# Supply_DAC.net
KiCad netlist of a schematic drawn in Altium Designer
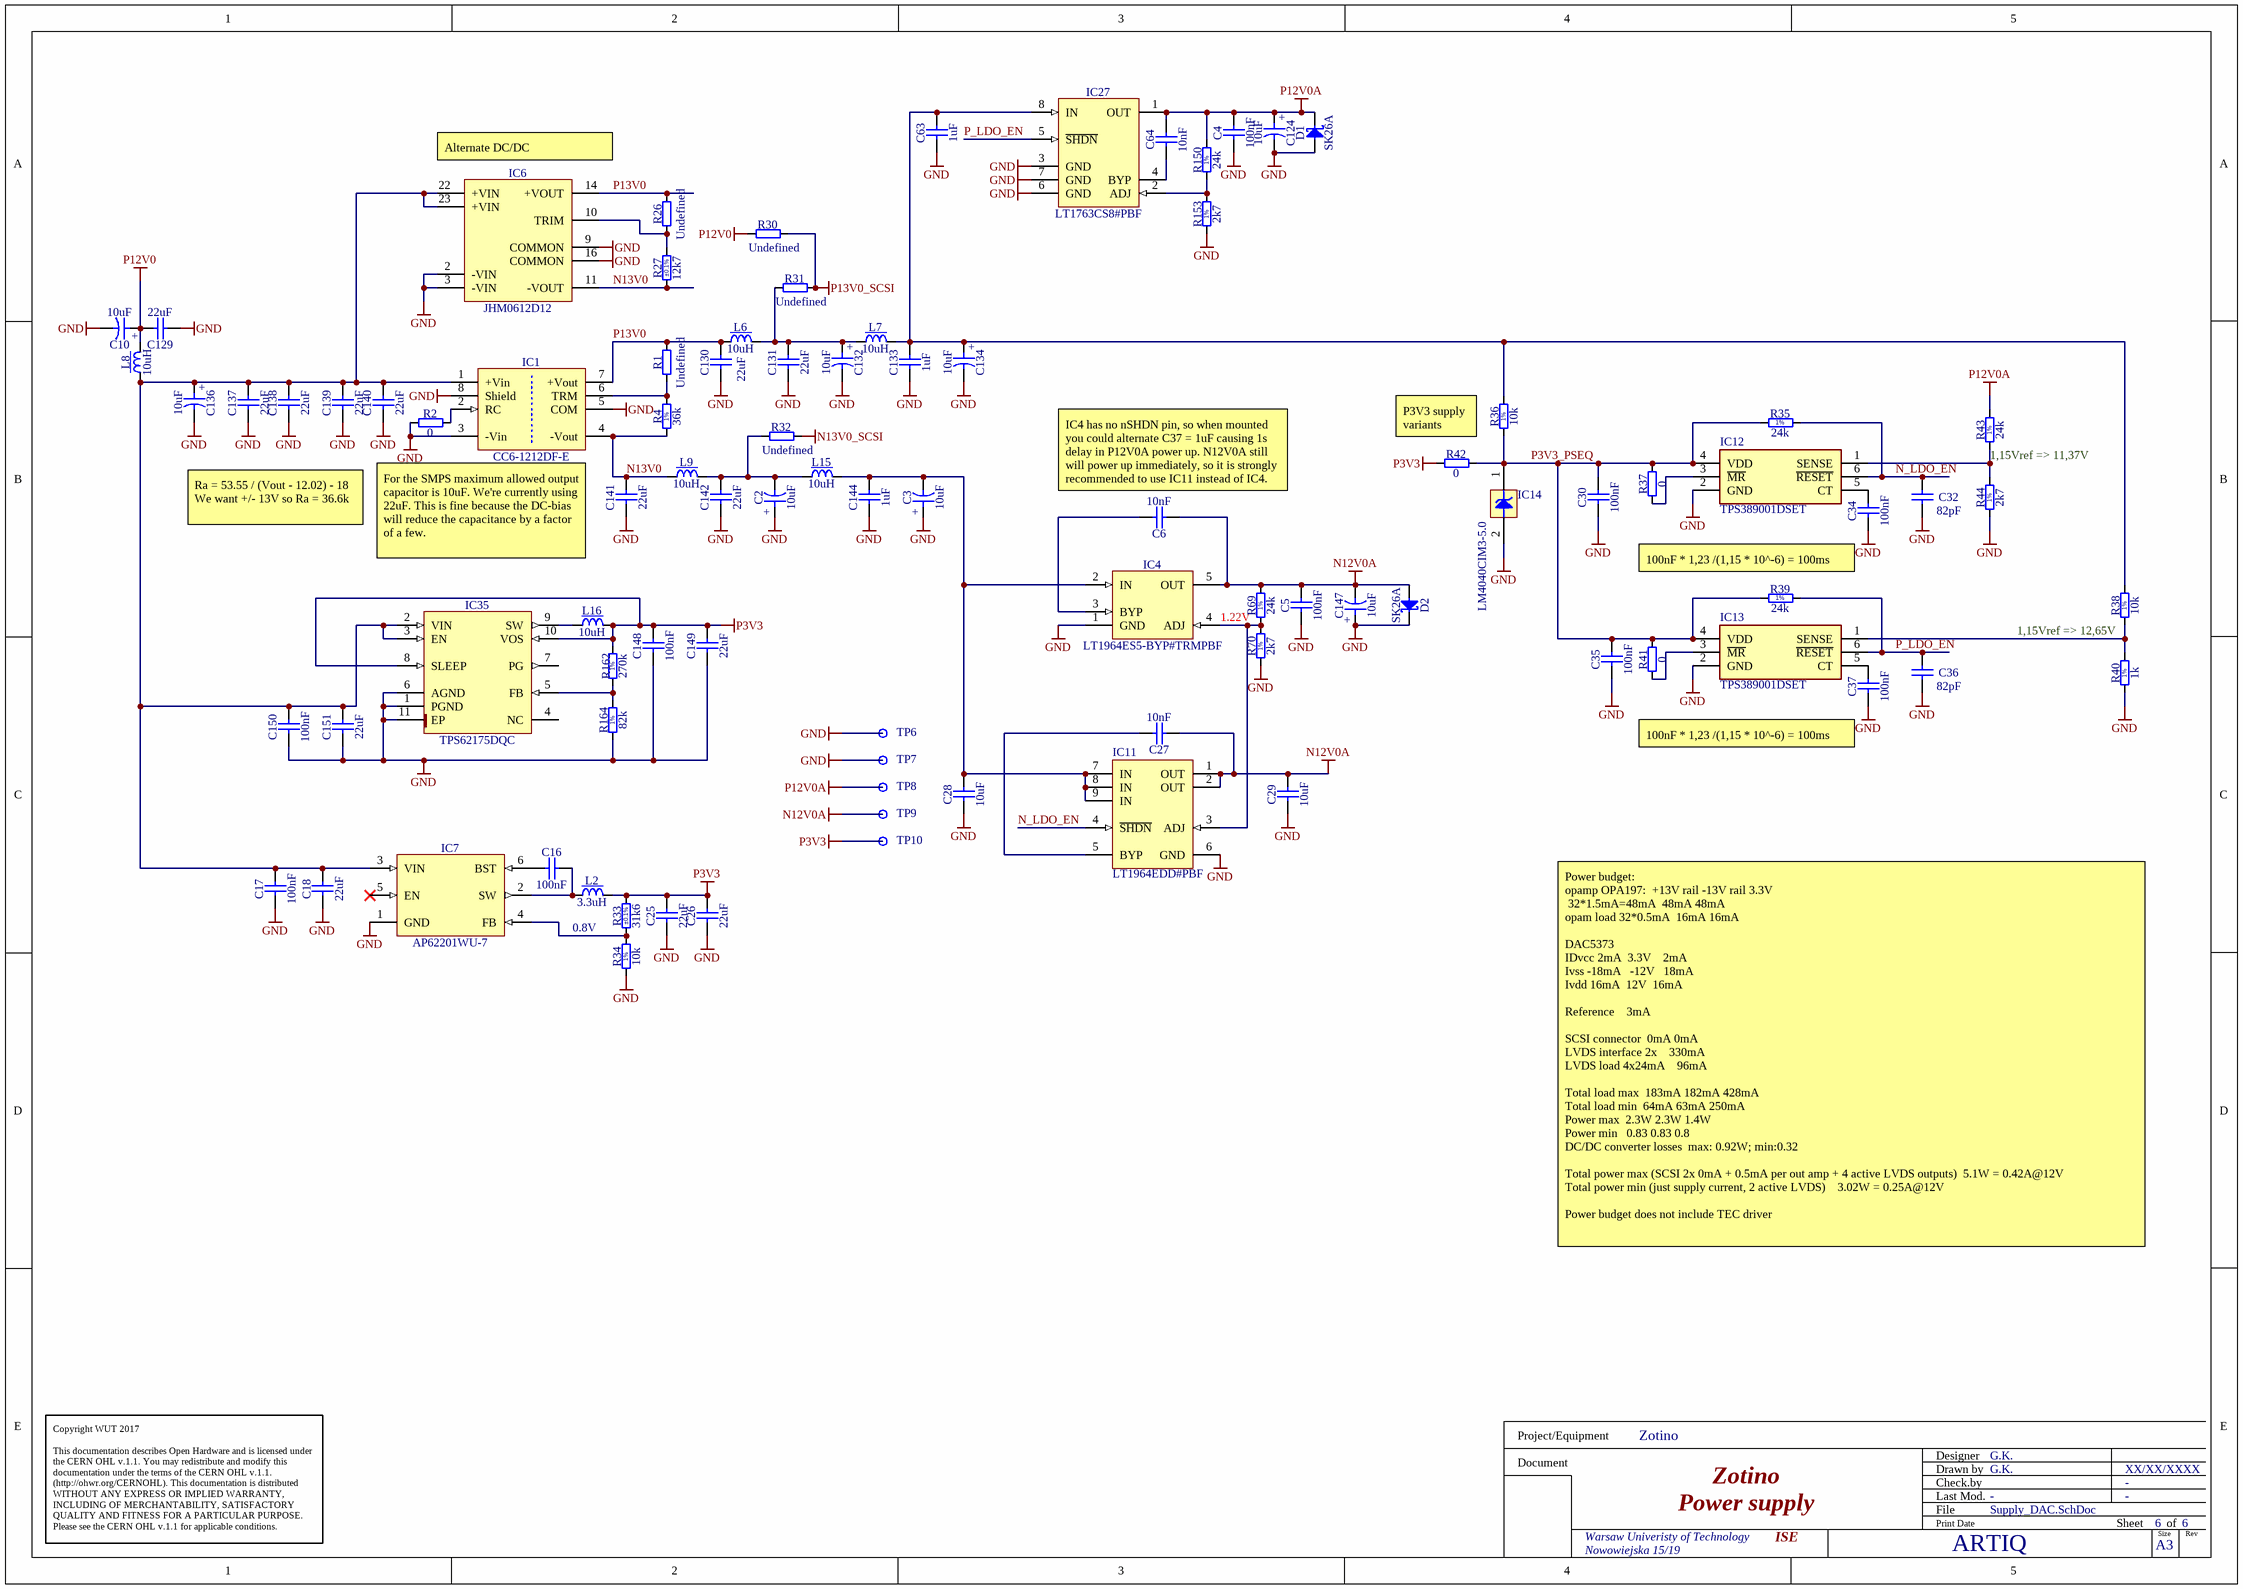
[diagram p0: Supply_DAC.SchDoc]

(export (version "E")
  (design (tool "Eeschema 10.0.6"))
  (components
    (comp (ref "C2")
      (value "10uF")
      (footprint "CAPMP3216X180N")
      (description "Polarised capacitor")
      (fields
        (field (name "PART NUMBER") "CTE3216-18_10UF_16V_20%_AVX_TCJ")
        (field (name "VOLTAGE") "16V")
        (field (name "AUTHOR") "CERN DEM JLC")
      )
      (libsource (lib "Capacitors") (part "Capacitor - polarized"))
    )
    (comp (ref "C3")
      (value "10uF")
      (footprint "CAPMP3216X180N")
      (description "Polarised capacitor")
      (fields
        (field (name "PART NUMBER") "CTE3216-18_10UF_16V_20%_AVX_TCJ")
        (field (name "VOLTAGE") "16V")
        (field (name "AUTHOR") "CERN DEM JLC")
      )
      (libsource (lib "Capacitors") (part "Capacitor - polarized"))
    )
    (comp (ref "C4")
      (value "100nF")
      (footprint "CAPC1005X55N")
      (description "Non-polarised capacitor")
      (fields
        (field (name "PART NUMBER") "CC0402_100NF_16V_10%_X5R")
        (field (name "VOLTAGE") "16V")
        (field (name "AUTHOR") "CERN DEM JLC")
      )
      (libsource (lib "Capacitors") (part "Capacitor - non polarized"))
    )
    (comp (ref "C5")
      (value "100nF")
      (footprint "CAPC1005X55N")
      (description "Non-polarised capacitor")
      (fields
        (field (name "PART NUMBER") "CC0402_100NF_16V_10%_X5R")
        (field (name "VOLTAGE") "16V")
        (field (name "AUTHOR") "CERN DEM JLC")
      )
      (libsource (lib "Capacitors") (part "Capacitor - non polarized"))
    )
    (comp (ref "C6")
      (value "10nF")
      (footprint "CAPC1608X87N")
      (description "Non-polarised capacitor")
      (fields
        (field (name "PART NUMBER") "CC0603_10NF_50V_10%_X7R")
        (field (name "VOLTAGE") "50V")
        (field (name "AUTHOR") "CERN DEM JLC")
      )
      (libsource (lib "Capacitors") (part "Capacitor - non polarized"))
    )
    (comp (ref "C10")
      (value "10uF")
      (footprint "CAPMP3216X180N")
      (description "Polarised capacitor")
      (fields
        (field (name "PART NUMBER") "CTE3216-18_10UF_16V_20%_AVX_TCJ")
        (field (name "VOLTAGE") "16V")
        (field (name "AUTHOR") "CERN DEM JLC")
      )
      (libsource (lib "Capacitors") (part "Capacitor - polarized"))
    )
    (comp (ref "C16")
      (value "100nF")
      (footprint "CAPC1005X55N")
      (description "Non-polarised capacitor")
      (fields
        (field (name "PART NUMBER") "CC0402_100NF_16V_10%_X5R")
        (field (name "VOLTAGE") "16V")
        (field (name "AUTHOR") "CERN DEM JLC")
      )
      (libsource (lib "Capacitors") (part "Capacitor - non polarized"))
    )
    (comp (ref "C17")
      (value "100nF")
      (footprint "CAPC1005X55N")
      (description "Non-polarised capacitor")
      (fields
        (field (name "PART NUMBER") "CC0402_100NF_16V_10%_X5R")
        (field (name "VOLTAGE") "16V")
        (field (name "AUTHOR") "CERN DEM JLC")
      )
      (libsource (lib "Capacitors") (part "Capacitor - non polarized"))
    )
    (comp (ref "C18")
      (value "22uF")
      (footprint "CAPC2012X135N")
      (description "Non-polarised capacitor")
      (fields
        (field (name "PART NUMBER") "CC0805_22UF_16V_10%_X5R")
        (field (name "VOLTAGE") "16V")
        (field (name "AUTHOR") "CERN DEM JLC")
      )
      (libsource (lib "Capacitors") (part "Capacitor - non polarized"))
    )
    (comp (ref "C25")
      (value "22uF")
      (footprint "CAPC2012X135N")
      (description "Non-polarised capacitor")
      (fields
        (field (name "PART NUMBER") "CC0805_22UF_16V_10%_X5R")
        (field (name "VOLTAGE") "16V")
        (field (name "AUTHOR") "CERN DEM JLC")
      )
      (libsource (lib "Capacitors") (part "Capacitor - non polarized"))
    )
    (comp (ref "C26")
      (value "22uF")
      (footprint "CAPC2012X135N")
      (description "Non-polarised capacitor")
      (fields
        (field (name "PART NUMBER") "CC0805_22UF_16V_10%_X5R")
        (field (name "VOLTAGE") "16V")
        (field (name "AUTHOR") "CERN DEM JLC")
      )
      (libsource (lib "Capacitors") (part "Capacitor - non polarized"))
    )
    (comp (ref "C27")
      (value "10nF")
      (footprint "CAPC1608X87N")
      (description "Non-polarised capacitor")
      (fields
        (field (name "PART NUMBER") "CC0603_10NF_50V_10%_X7R")
        (field (name "VOLTAGE") "50V")
        (field (name "AUTHOR") "CERN DEM JLC")
      )
      (libsource (lib "Capacitors") (part "Capacitor - non polarized"))
    )
    (comp (ref "C28")
      (value "10uF")
      (footprint "CAPC1608X80N")
      (description "Non-polarised capacitor")
      (fields
        (field (name "PART NUMBER") "CC0603_10UF_16V_20%_X5R")
        (field (name "VOLTAGE") "16V")
        (field (name "AUTHOR") "CERN DEM MR")
      )
      (libsource (lib "Capacitors") (part "Capacitor - non polarized"))
    )
    (comp (ref "C29")
      (value "10uF")
      (footprint "CAPC1608X80N")
      (description "Non-polarised capacitor")
      (fields
        (field (name "PART NUMBER") "CC0603_10UF_16V_20%_X5R")
        (field (name "VOLTAGE") "16V")
        (field (name "AUTHOR") "CERN DEM MR")
      )
      (libsource (lib "Capacitors") (part "Capacitor - non polarized"))
    )
    (comp (ref "C30")
      (value "100nF")
      (footprint "CAPC1005X55N")
      (description "Non-polarised capacitor")
      (fields
        (field (name "PART NUMBER") "CC0402_100NF_16V_10%_X5R")
        (field (name "VOLTAGE") "16V")
        (field (name "AUTHOR") "CERN DEM JLC")
      )
      (libsource (lib "Capacitors") (part "Capacitor - non polarized"))
    )
    (comp (ref "C32")
      (value "82pF")
      (footprint "CAPC1608X87N")
      (description "Non-polarised capacitor")
      (fields
        (field (name "PART NUMBER") "CC0603_82PF_50V_5%_NP0")
        (field (name "VOLTAGE") "50V")
        (field (name "AUTHOR") "CERN DEM JLC")
      )
      (libsource (lib "Capacitors") (part "Capacitor - non polarized"))
    )
    (comp (ref "C34")
      (value "100nF")
      (footprint "CAPC1005X55N")
      (description "Non-polarised capacitor")
      (fields
        (field (name "PART NUMBER") "CC0402_100NF_16V_10%_X5R")
        (field (name "VOLTAGE") "16V")
        (field (name "AUTHOR") "CERN DEM JLC")
      )
      (libsource (lib "Capacitors") (part "Capacitor - non polarized"))
    )
    (comp (ref "C35")
      (value "100nF")
      (footprint "CAPC1005X55N")
      (description "Non-polarised capacitor")
      (fields
        (field (name "PART NUMBER") "CC0402_100NF_16V_10%_X5R")
        (field (name "VOLTAGE") "16V")
        (field (name "AUTHOR") "CERN DEM JLC")
      )
      (libsource (lib "Capacitors") (part "Capacitor - non polarized"))
    )
    (comp (ref "C36")
      (value "82pF")
      (footprint "CAPC1608X87N")
      (description "Non-polarised capacitor")
      (fields
        (field (name "PART NUMBER") "CC0603_82PF_50V_5%_NP0")
        (field (name "VOLTAGE") "50V")
        (field (name "AUTHOR") "CERN DEM JLC")
      )
      (libsource (lib "Capacitors") (part "Capacitor - non polarized"))
    )
    (comp (ref "C37")
      (value "100nF")
      (footprint "CAPC1005X55N")
      (description "Non-polarised capacitor")
      (fields
        (field (name "PART NUMBER") "CC0402_100NF_16V_10%_X5R")
        (field (name "VOLTAGE") "16V")
        (field (name "AUTHOR") "CERN DEM JLC")
      )
      (libsource (lib "Capacitors") (part "Capacitor - non polarized"))
    )
    (comp (ref "C63")
      (value "1uF")
      (footprint "CAPC1608X87N")
      (description "Non-polarised capacitor")
      (fields
        (field (name "PART NUMBER") "CC0603_1UF_25V_10%_X7R")
        (field (name "VOLTAGE") "25V")
        (field (name "AUTHOR") "CERN DEM JLC")
      )
      (libsource (lib "Capacitors") (part "Capacitor - non polarized"))
    )
    (comp (ref "C64")
      (value "10nF")
      (footprint "CAPC1608X87N")
      (description "Non-polarised capacitor")
      (fields
        (field (name "PART NUMBER") "CC0603_10NF_50V_10%_X7R")
        (field (name "VOLTAGE") "50V")
        (field (name "AUTHOR") "CERN DEM JLC")
      )
      (libsource (lib "Capacitors") (part "Capacitor - non polarized"))
    )
    (comp (ref "C124")
      (value "10uF")
      (footprint "CAPMP3216X180N")
      (description "Polarised capacitor")
      (fields
        (field (name "PART NUMBER") "CTE3216-18_10UF_16V_20%_AVX_TCJ")
        (field (name "VOLTAGE") "16V")
        (field (name "AUTHOR") "CERN DEM JLC")
      )
      (libsource (lib "Capacitors") (part "Capacitor - polarized"))
    )
    (comp (ref "C129")
      (value "22uF")
      (footprint "CAPC2012X135N")
      (description "Non-polarised capacitor")
      (fields
        (field (name "PART NUMBER") "CC0805_22UF_16V_10%_X5R")
        (field (name "VOLTAGE") "16V")
        (field (name "AUTHOR") "CERN DEM JLC")
      )
      (libsource (lib "Capacitors") (part "Capacitor - non polarized"))
    )
    (comp (ref "C130")
      (value "22uF")
      (footprint "CAPC2012X135N")
      (description "Non-polarised capacitor")
      (fields
        (field (name "PART NUMBER") "CC0805_22UF_16V_10%_X5R")
        (field (name "VOLTAGE") "16V")
        (field (name "AUTHOR") "CERN DEM JLC")
      )
      (libsource (lib "Capacitors") (part "Capacitor - non polarized"))
    )
    (comp (ref "C131")
      (value "22uF")
      (footprint "CAPC2012X135N")
      (description "Non-polarised capacitor")
      (fields
        (field (name "PART NUMBER") "CC0805_22UF_16V_10%_X5R")
        (field (name "VOLTAGE") "16V")
        (field (name "AUTHOR") "CERN DEM JLC")
      )
      (libsource (lib "Capacitors") (part "Capacitor - non polarized"))
    )
    (comp (ref "C132")
      (value "10uF")
      (footprint "CAPMP3216X180N")
      (description "Polarised capacitor")
      (fields
        (field (name "PART NUMBER") "CTE3216-18_10UF_16V_20%_AVX_TCJ")
        (field (name "VOLTAGE") "16V")
        (field (name "AUTHOR") "CERN DEM JLC")
      )
      (libsource (lib "Capacitors") (part "Capacitor - polarized"))
    )
    (comp (ref "C133")
      (value "1uF")
      (footprint "CAPC1608X87N")
      (description "Non-polarised capacitor")
      (fields
        (field (name "PART NUMBER") "CC0603_1UF_25V_10%_X7R")
        (field (name "VOLTAGE") "25V")
        (field (name "AUTHOR") "CERN DEM JLC")
      )
      (libsource (lib "Capacitors") (part "Capacitor - non polarized"))
    )
    (comp (ref "C134")
      (value "10uF")
      (footprint "CAPMP3216X180N")
      (description "Polarised capacitor")
      (fields
        (field (name "PART NUMBER") "CTE3216-18_10UF_16V_20%_AVX_TCJ")
        (field (name "VOLTAGE") "16V")
        (field (name "AUTHOR") "CERN DEM JLC")
      )
      (libsource (lib "Capacitors") (part "Capacitor - polarized"))
    )
    (comp (ref "C136")
      (value "10uF")
      (footprint "CAPMP3216X180N")
      (description "Polarised capacitor")
      (fields
        (field (name "PART NUMBER") "CTE3216-18_10UF_16V_20%_AVX_TCJ")
        (field (name "VOLTAGE") "16V")
        (field (name "AUTHOR") "CERN DEM JLC")
      )
      (libsource (lib "Capacitors") (part "Capacitor - polarized"))
    )
    (comp (ref "C137")
      (value "22uF")
      (footprint "CAPC2012X135N")
      (description "Non-polarised capacitor")
      (fields
        (field (name "PART NUMBER") "CC0805_22UF_16V_10%_X5R")
        (field (name "VOLTAGE") "16V")
        (field (name "AUTHOR") "CERN DEM JLC")
      )
      (libsource (lib "Capacitors") (part "Capacitor - non polarized"))
    )
    (comp (ref "C138")
      (value "22uF")
      (footprint "CAPC2012X135N")
      (description "Non-polarised capacitor")
      (fields
        (field (name "PART NUMBER") "CC0805_22UF_16V_10%_X5R")
        (field (name "VOLTAGE") "16V")
        (field (name "AUTHOR") "CERN DEM JLC")
      )
      (libsource (lib "Capacitors") (part "Capacitor - non polarized"))
    )
    (comp (ref "C139")
      (value "22uF")
      (footprint "CAPC2012X135N")
      (description "Non-polarised capacitor")
      (fields
        (field (name "PART NUMBER") "CC0805_22UF_16V_10%_X5R")
        (field (name "VOLTAGE") "16V")
        (field (name "AUTHOR") "CERN DEM JLC")
      )
      (libsource (lib "Capacitors") (part "Capacitor - non polarized"))
    )
    (comp (ref "C140")
      (value "22uF")
      (footprint "CAPC2012X135N")
      (description "Non-polarised capacitor")
      (fields
        (field (name "PART NUMBER") "CC0805_22UF_16V_10%_X5R")
        (field (name "VOLTAGE") "16V")
        (field (name "AUTHOR") "CERN DEM JLC")
      )
      (libsource (lib "Capacitors") (part "Capacitor - non polarized"))
    )
    (comp (ref "C141")
      (value "22uF")
      (footprint "CAPC2012X135N")
      (description "Non-polarised capacitor")
      (fields
        (field (name "PART NUMBER") "CC0805_22UF_16V_10%_X5R")
        (field (name "VOLTAGE") "16V")
        (field (name "AUTHOR") "CERN DEM JLC")
      )
      (libsource (lib "Capacitors") (part "Capacitor - non polarized"))
    )
    (comp (ref "C142")
      (value "22uF")
      (footprint "CAPC2012X135N")
      (description "Non-polarised capacitor")
      (fields
        (field (name "PART NUMBER") "CC0805_22UF_16V_10%_X5R")
        (field (name "VOLTAGE") "16V")
        (field (name "AUTHOR") "CERN DEM JLC")
      )
      (libsource (lib "Capacitors") (part "Capacitor - non polarized"))
    )
    (comp (ref "C144")
      (value "1uF")
      (footprint "CAPC1608X87N")
      (description "Non-polarised capacitor")
      (fields
        (field (name "PART NUMBER") "CC0603_1UF_25V_10%_X7R")
        (field (name "VOLTAGE") "25V")
        (field (name "AUTHOR") "CERN DEM JLC")
      )
      (libsource (lib "Capacitors") (part "Capacitor - non polarized"))
    )
    (comp (ref "C147")
      (value "10uF")
      (footprint "CAPMP3216X180N")
      (description "Polarised capacitor")
      (fields
        (field (name "PART NUMBER") "CTE3216-18_10UF_16V_20%_AVX_TCJ")
        (field (name "VOLTAGE") "16V")
        (field (name "AUTHOR") "CERN DEM JLC")
      )
      (libsource (lib "Capacitors") (part "Capacitor - polarized"))
    )
    (comp (ref "C148")
      (value "100nF")
      (footprint "CAPC1005X55N")
      (description "Non-polarised capacitor")
      (fields
        (field (name "PART NUMBER") "CC0402_100NF_16V_10%_X5R")
        (field (name "VOLTAGE") "16V")
        (field (name "AUTHOR") "CERN DEM JLC")
      )
      (libsource (lib "Capacitors") (part "Capacitor - non polarized"))
    )
    (comp (ref "C149")
      (value "22uF")
      (footprint "CAPC2012X135N")
      (description "Non-polarised capacitor")
      (fields
        (field (name "PART NUMBER") "CC0805_22UF_16V_10%_X5R")
        (field (name "VOLTAGE") "16V")
        (field (name "AUTHOR") "CERN DEM JLC")
      )
      (libsource (lib "Capacitors") (part "Capacitor - non polarized"))
    )
    (comp (ref "C150")
      (value "100nF")
      (footprint "CAPC1005X55N")
      (description "Non-polarised capacitor")
      (fields
        (field (name "PART NUMBER") "CC0402_100NF_16V_10%_X5R")
        (field (name "VOLTAGE") "16V")
        (field (name "AUTHOR") "CERN DEM JLC")
      )
      (libsource (lib "Capacitors") (part "Capacitor - non polarized"))
    )
    (comp (ref "C151")
      (value "22uF")
      (footprint "CAPC2012X135N")
      (description "Non-polarised capacitor")
      (fields
        (field (name "PART NUMBER") "CC0805_22UF_16V_10%_X5R")
        (field (name "VOLTAGE") "16V")
        (field (name "AUTHOR") "CERN DEM JLC")
      )
      (libsource (lib "Capacitors") (part "Capacitor - non polarized"))
    )
    (comp (ref "D1")
      (value "SK26A")
      (footprint "DIOM5126X265N")
      (description "Schottky Diode")
      (fields
        (field (name "VOLTAGE") "60V")
        (field (name "POWER") "2A")
        (field (name "AUTHOR") "CERN DEM JMW")
      )
      (libsource (lib "ICs And Semiconductors") (part "Diode Schottky"))
    )
    (comp (ref "D2")
      (value "SK26A")
      (footprint "DIOM5126X265N")
      (description "Schottky Diode")
      (fields
        (field (name "VOLTAGE") "60V")
        (field (name "POWER") "2A")
        (field (name "AUTHOR") "CERN DEM JMW")
      )
      (libsource (lib "ICs And Semiconductors") (part "Diode Schottky"))
    )
    (comp (ref "IC1")
      (value "CC6-1212DF-E")
      (footprint "CC6-1212DF-E")
      (description "CONV DC/DC 6W DUAL 12V +-12V PCB")
      (fields (field (name "MANUFACTURER") "TDK-Lambda Americas Inc.") (field (name "AUTHOR") "GK"))
      (libsource (lib "Regulators_SMPS") (part "DC/DC_CC6-1212DF-E"))
    )
    (comp (ref "IC4")
      (value "LT1964ES5-BYP#TRMPBF")
      (footprint "SOT95P280X100-5N")
      (description "200mA, Low Noise, Low Dropout Negative Micropower Regulator")
      (fields (field (name "MANUFACTURER") "LINEAR TECHNOLOGY") (field (name "AUTHOR") "CERN DEM MR"))
      (libsource (lib "ICs And Semiconductors") (part "LT1964-BYP"))
    )
    (comp (ref "IC6")
      (value "JHM0612D12")
      (footprint "DCDC_XPPOWER_JHM0X")
      (description "9-72VDC to 3.3-15VDC, Iout (max) 500mA, DC-DC Converter")
      (fields (field (name "MANUFACTURER") "XP POWER") (field (name "AUTHOR") "CERN DEM HF"))
      (libsource (lib "ICs And Semiconductors") (part "DCDC_XPPOWER_JHM0xxxD"))
    )
    (comp (ref "IC7")
      (value "AP62201WU-7")
      (footprint "SOT95P280X100-6N")
      (description "4.2V TO 18V INPUT, 2A LOW IQ SYNCHRONOUS BUCK CONVERTER")
      (fields
        (field (name "MANUFACTURER") "DIODES INCORPORATED")
        (field (name "MANUFACTURER PART NUMBER") "AP62201WU")
        (field (name "AUTHOR") "CERN DEM HF")
      )
      (libsource (lib "ICs And Semiconductors") (part "AP62201WU"))
    )
    (comp (ref "IC11")
      (value "LT1964EDD#PBF")
      (footprint "LT-DD-8_V")
      (fields (field (name "MANUFACTURER") "Linear Technology"))
      (libsource (lib "Altium Content Vault") (part "LT-LT1964-DD-8"))
    )
    (comp (ref "IC12")
      (value "TPS389001DSET")
      (footprint "TPS610985DSET")
      (description "Supervisory Circuits Low-quiescent current 1% accuracy supervisor with programmable delay")
      (fields (field (name "MOUSER PART NUMBER") "595-TPS389001DSET"))
      (libsource (lib "Integrated_Library_LOADER") (part "TPS389001DSET"))
    )
    (comp (ref "IC13")
      (value "TPS389001DSET")
      (footprint "TPS610985DSET")
      (description "Supervisory Circuits Low-quiescent current 1% accuracy supervisor with programmable delay")
      (fields (field (name "MOUSER PART NUMBER") "595-TPS389001DSET"))
      (libsource (lib "Integrated_Library_LOADER") (part "TPS389001DSET"))
    )
    (comp (ref "IC14")
      (value "LM4040CIM3-5.0")
      (footprint "SOT95P237X112-3N")
      (description "Integrated Circuit")
      (fields (field (name "MOUSER PART NUMBER") "926-LM4040CIM3-50"))
      (libsource (lib "Integrated_Library_LOADER") (part "LM4040CIM3-5.0"))
    )
    (comp (ref "IC27")
      (value "LT1763CS8#PBF")
      (footprint "SOIC127P600X175-8N")
      (description "1.22V to 20V 500mA, Low Noise, LDO Adjustable Micropower Regulator")
      (fields (field (name "MANUFACTURER") "LINEAR TECHNOLOGY") (field (name "AUTHOR") "CERN DEM JLC"))
      (libsource (lib "ICs And Semiconductors") (part "LT1763xS8"))
    )
    (comp (ref "IC35")
      (value "TPS62175DQC")
      (footprint "SON50P200X300X80-11N-R94X250")
      (description "4.75-28VDC to 1-6VDC, 500mA Step-Down Converter With Sleep Mode")
      (fields (field (name "MANUFACTURER") "TEXAS INSTRUMENTS") (field (name "AUTHOR") "CERN DEM JMW"))
      (libsource (lib "ICs And Semiconductors") (part "TPS62175"))
    )
    (comp (ref "L2")
      (value "3.3uH")
      (footprint "IND_WURTH_WE-TPC_4828")
      (description "Inductor With Core")
      (fields
        (field (name "PART NUMBER") "IND_3.3UH_30%_WURTH_WE-TPC_744043003")
        (field (name "POWER") "2.15A")
        (field (name "AUTHOR") "CERN DEM JLC")
      )
      (libsource (lib "Inductors & Transformers") (part "Inductor With Magnetic core"))
    )
    (comp (ref "L6")
      (value "10uH")
      (footprint "IND_MURATA-PS_8400")
      (description "Inductor With Core")
      (fields
        (field (name "PART NUMBER") "IND_10UH_10%_MURATA-PS_8400")
        (field (name "POWER") "950mA")
        (field (name "AUTHOR") "CERN DEM JLC")
      )
      (libsource (lib "Inductors & Transformers") (part "Inductor With Magnetic core"))
    )
    (comp (ref "L7")
      (value "10uH")
      (footprint "IND_MURATA-PS_8400")
      (description "Inductor With Core")
      (fields
        (field (name "PART NUMBER") "IND_10UH_10%_MURATA-PS_8400")
        (field (name "POWER") "950mA")
        (field (name "AUTHOR") "CERN DEM JLC")
      )
      (libsource (lib "Inductors & Transformers") (part "Inductor With Magnetic core"))
    )
    (comp (ref "L8")
      (value "10uH")
      (footprint "IND_MURATA-PS_8400")
      (description "Inductor With Core")
      (fields
        (field (name "PART NUMBER") "IND_10UH_10%_MURATA-PS_8400")
        (field (name "POWER") "950mA")
        (field (name "AUTHOR") "CERN DEM JLC")
      )
      (libsource (lib "") (part "Inductor With Magnetic core_1"))
    )
    (comp (ref "L9")
      (value "10uH")
      (footprint "IND_MURATA-PS_8400")
      (description "Inductor With Core")
      (fields
        (field (name "PART NUMBER") "IND_10UH_10%_MURATA-PS_8400")
        (field (name "POWER") "950mA")
        (field (name "AUTHOR") "CERN DEM JLC")
      )
      (libsource (lib "Inductors & Transformers") (part "Inductor With Magnetic core"))
    )
    (comp (ref "L15")
      (value "10uH")
      (footprint "IND_MURATA-PS_8400")
      (description "Inductor With Core")
      (fields
        (field (name "PART NUMBER") "IND_10UH_10%_MURATA-PS_8400")
        (field (name "POWER") "950mA")
        (field (name "AUTHOR") "CERN DEM JLC")
      )
      (libsource (lib "Inductors & Transformers") (part "Inductor With Magnetic core"))
    )
    (comp (ref "L16")
      (value "10uH")
      (footprint "IND_MURATA-PS_8400")
      (description "Inductor With Core")
      (fields
        (field (name "PART NUMBER") "IND_10UH_10%_MURATA-PS_8400")
        (field (name "POWER") "950mA")
        (field (name "AUTHOR") "CERN DEM JLC")
      )
      (libsource (lib "Inductors & Transformers") (part "Inductor With Magnetic core"))
    )
    (comp (ref "R1")
      (value "Undefined")
      (footprint "RESC1608X55N")
      (description "Resistor")
      (fields (field (name "PART NUMBER") "R0603_NO-VALUE") (field (name "AUTHOR") "CERN DEM JLC"))
      (libsource (lib "Resistors") (part "Resistor"))
    )
    (comp (ref "R2")
      (value "0")
      (footprint "RESC1005X40N")
      (description "Resistor")
      (fields
        (field (name "PART NUMBER") "R0402_0R_JUMPER")
        (field (name "MANUFACTURER") "GENERIC")
        (field (name "AUTHOR") "CERN DEM JLC")
      )
      (libsource (lib "Resistors") (part "Resistor"))
    )
    (comp (ref "R4")
      (value "36k")
      (footprint "RESC1608X55N")
      (description "Resistor - 1%")
      (fields
        (field (name "PART NUMBER") "R0603_36K_1%_0.1W_100PPM")
        (field (name "POWER") "0.1W")
        (field (name "AUTHOR") "CERN DEM JLC")
      )
      (libsource (lib "Resistors") (part "Resistor - 1%"))
    )
    (comp (ref "R26")
      (value "Undefined")
      (footprint "RESC1608X55N")
      (description "Resistor")
      (fields (field (name "PART NUMBER") "R0603_NO-VALUE") (field (name "AUTHOR") "CERN DEM JLC"))
      (libsource (lib "Resistors") (part "Resistor"))
    )
    (comp (ref "R27")
      (value "12k7")
      (footprint "RESC1608X55N")
      (description "Resistor - 0.1%")
      (fields
        (field (name "TOLERANCE") "±0.1%")
        (field (name "PART NUMBER") "R0603_12K7_0.1%_0.063W_10PPM")
        (field (name "POWER") "0.063W")
        (field (name "AUTHOR") "CERN DEM JLC")
      )
      (libsource (lib "Resistors") (part "Resistor - 0.1%"))
    )
    (comp (ref "R30")
      (value "Undefined")
      (footprint "RESC3216X65N")
      (description "Resistor")
      (fields (field (name "PART NUMBER") "R1206_NO-VALUE") (field (name "AUTHOR") "CERN DEM JLC"))
      (libsource (lib "Resistors") (part "Resistor"))
    )
    (comp (ref "R31")
      (value "Undefined")
      (footprint "RESC3216X65N")
      (description "Resistor")
      (fields (field (name "PART NUMBER") "R1206_NO-VALUE") (field (name "AUTHOR") "CERN DEM JLC"))
      (libsource (lib "Resistors") (part "Resistor"))
    )
    (comp (ref "R32")
      (value "Undefined")
      (footprint "RESC3216X65N")
      (description "Resistor")
      (fields (field (name "PART NUMBER") "R1206_NO-VALUE") (field (name "AUTHOR") "CERN DEM JLC"))
      (libsource (lib "Resistors") (part "Resistor"))
    )
    (comp (ref "R33")
      (value "31k6")
      (footprint "RESC1005X35N")
      (description "Resistor - 0.1%")
      (fields
        (field (name "TOLERANCE") "±0.1%")
        (field (name "PART NUMBER") "R0402_31K6_0.1%_0.063W_25PPM_YAGEO_RT")
        (field (name "POWER") "0.063W")
        (field (name "AUTHOR") "CERN DEM BC")
      )
      (libsource (lib "Resistors") (part "Resistor - 0.1%"))
    )
    (comp (ref "R34")
      (value "10k")
      (footprint "RESC1005X40N")
      (description "Resistor - 1%")
      (fields
        (field (name "PART NUMBER") "R0402_10K_1%_0.0625W_100PPM")
        (field (name "POWER") "0.0625W")
        (field (name "AUTHOR") "CERN DEM JLC")
      )
      (libsource (lib "Resistors") (part "Resistor - 1%"))
    )
    (comp (ref "R35")
      (value "24k")
      (footprint "RESC1608X55N")
      (description "Resistor - 1%")
      (fields
        (field (name "PART NUMBER") "R0603_24K_1%_0.1W_100PPM")
        (field (name "POWER") "0.1W")
        (field (name "AUTHOR") "CERN DEM JLC")
      )
      (libsource (lib "Resistors") (part "Resistor - 1%"))
    )
    (comp (ref "R36")
      (value "10k")
      (footprint "RESC1005X40N")
      (description "Resistor - 1%")
      (fields
        (field (name "PART NUMBER") "R0402_10K_1%_0.0625W_100PPM")
        (field (name "POWER") "0.0625W")
        (field (name "AUTHOR") "CERN DEM JLC")
      )
      (libsource (lib "Resistors") (part "Resistor - 1%"))
    )
    (comp (ref "R37")
      (value "0")
      (footprint "RESC1005X40N")
      (description "Resistor")
      (fields
        (field (name "PART NUMBER") "R0402_0R_JUMPER")
        (field (name "MANUFACTURER") "GENERIC")
        (field (name "AUTHOR") "CERN DEM JLC")
      )
      (libsource (lib "Resistors") (part "Resistor"))
    )
    (comp (ref "R38")
      (value "10k")
      (footprint "RESC1005X40N")
      (description "Resistor - 1%")
      (fields
        (field (name "PART NUMBER") "R0402_10K_1%_0.0625W_100PPM")
        (field (name "POWER") "0.0625W")
        (field (name "AUTHOR") "CERN DEM JLC")
      )
      (libsource (lib "Resistors") (part "Resistor - 1%"))
    )
    (comp (ref "R39")
      (value "24k")
      (footprint "RESC1608X55N")
      (description "Resistor - 1%")
      (fields
        (field (name "PART NUMBER") "R0603_24K_1%_0.1W_100PPM")
        (field (name "POWER") "0.1W")
        (field (name "AUTHOR") "CERN DEM JLC")
      )
      (libsource (lib "Resistors") (part "Resistor - 1%"))
    )
    (comp (ref "R40")
      (value "1k")
      (footprint "RESC1608X55N")
      (description "Resistor - 1%")
      (fields
        (field (name "PART NUMBER") "R0603_1K_1%_0.1W_100PPM")
        (field (name "POWER") "0.1W")
        (field (name "AUTHOR") "CERN DEM JLC")
      )
      (libsource (lib "Resistors") (part "Resistor - 1%"))
    )
    (comp (ref "R41")
      (value "0")
      (footprint "RESC1005X40N")
      (description "Resistor")
      (fields
        (field (name "PART NUMBER") "R0402_0R_JUMPER")
        (field (name "MANUFACTURER") "GENERIC")
        (field (name "AUTHOR") "CERN DEM JLC")
      )
      (libsource (lib "Resistors") (part "Resistor"))
    )
    (comp (ref "R42")
      (value "0")
      (footprint "RESC1005X40N")
      (description "Resistor")
      (fields
        (field (name "PART NUMBER") "R0402_0R_JUMPER")
        (field (name "MANUFACTURER") "GENERIC")
        (field (name "AUTHOR") "CERN DEM JLC")
      )
      (libsource (lib "Resistors") (part "Resistor"))
    )
    (comp (ref "R43")
      (value "24k")
      (footprint "RESC1608X55N")
      (description "Resistor - 1%")
      (fields
        (field (name "PART NUMBER") "R0603_24K_1%_0.1W_100PPM")
        (field (name "POWER") "0.1W")
        (field (name "AUTHOR") "CERN DEM JLC")
      )
      (libsource (lib "Resistors") (part "Resistor - 1%"))
    )
    (comp (ref "R44")
      (value "2k7")
      (footprint "RESC1608X55N")
      (description "Resistor - 1%")
      (fields
        (field (name "PART NUMBER") "R0603_2K7_1%_0.1W_100PPM")
        (field (name "POWER") "0.1W")
        (field (name "AUTHOR") "CERN DEM JLC")
      )
      (libsource (lib "Resistors") (part "Resistor - 1%"))
    )
    (comp (ref "R69")
      (value "24k")
      (footprint "RESC1608X55N")
      (description "Resistor - 1%")
      (fields
        (field (name "PART NUMBER") "R0603_24K_1%_0.1W_100PPM")
        (field (name "POWER") "0.1W")
        (field (name "AUTHOR") "CERN DEM JLC")
      )
      (libsource (lib "Resistors") (part "Resistor - 1%"))
    )
    (comp (ref "R70")
      (value "2k7")
      (footprint "RESC1608X55N")
      (description "Resistor - 1%")
      (fields
        (field (name "PART NUMBER") "R0603_2K7_1%_0.1W_100PPM")
        (field (name "POWER") "0.1W")
        (field (name "AUTHOR") "CERN DEM JLC")
      )
      (libsource (lib "Resistors") (part "Resistor - 1%"))
    )
    (comp (ref "R150")
      (value "24k")
      (footprint "RESC1608X55N")
      (description "Resistor - 1%")
      (fields
        (field (name "PART NUMBER") "R0603_24K_1%_0.1W_100PPM")
        (field (name "POWER") "0.1W")
        (field (name "AUTHOR") "CERN DEM JLC")
      )
      (libsource (lib "Resistors") (part "Resistor - 1%"))
    )
    (comp (ref "R153")
      (value "2k7")
      (footprint "RESC1608X55N")
      (description "Resistor - 1%")
      (fields
        (field (name "PART NUMBER") "R0603_2K7_1%_0.1W_100PPM")
        (field (name "POWER") "0.1W")
        (field (name "AUTHOR") "CERN DEM JLC")
      )
      (libsource (lib "Resistors") (part "Resistor - 1%"))
    )
    (comp (ref "R162")
      (value "270k")
      (footprint "RESC1608X55N")
      (description "Resistor - 1%")
      (fields
        (field (name "PART NUMBER") "R0603_270K_1%_0.1W_100PPM")
        (field (name "POWER") "0.1W")
        (field (name "AUTHOR") "CERN DEM JLC")
      )
      (libsource (lib "Resistors") (part "Resistor - 1%"))
    )
    (comp (ref "R164")
      (value "82k")
      (footprint "RESC1608X55N")
      (description "Resistor - 1%")
      (fields
        (field (name "PART NUMBER") "R0603_82K_1%_0.1W_100PPM")
        (field (name "POWER") "0.1W")
        (field (name "AUTHOR") "CERN DEM JLC")
      )
      (libsource (lib "Resistors") (part "Resistor - 1%"))
    )
    (comp (ref "TP6")
      (value "Test Point")
      (footprint "TPS127")
      (fields (field (name "PART NUMBER") "SMD_PAD_1.27X1.27MM") (field (name "AUTHOR") "CERN DEM JLC"))
      (libsource (lib "Eletro-mechanical") (part "Test Point"))
    )
    (comp (ref "TP7")
      (value "Test Point")
      (footprint "TPS127")
      (fields (field (name "PART NUMBER") "SMD_PAD_1.27X1.27MM") (field (name "AUTHOR") "CERN DEM JLC"))
      (libsource (lib "Eletro-mechanical") (part "Test Point"))
    )
    (comp (ref "TP8")
      (value "Test Point")
      (footprint "TPS127")
      (fields (field (name "PART NUMBER") "SMD_PAD_1.27X1.27MM") (field (name "AUTHOR") "CERN DEM JLC"))
      (libsource (lib "Eletro-mechanical") (part "Test Point"))
    )
    (comp (ref "TP9")
      (value "Test Point")
      (footprint "TPS127")
      (fields (field (name "PART NUMBER") "SMD_PAD_1.27X1.27MM") (field (name "AUTHOR") "CERN DEM JLC"))
      (libsource (lib "Eletro-mechanical") (part "Test Point"))
    )
    (comp (ref "TP10")
      (value "Test Point")
      (footprint "TPS127")
      (fields (field (name "PART NUMBER") "SMD_PAD_1.27X1.27MM") (field (name "AUTHOR") "CERN DEM JLC"))
      (libsource (lib "Eletro-mechanical") (part "Test Point"))
    )
  )
  (nets
    (net (code "1") (name "/N13V0") (class "Default")
      (node (ref "C141") (pin "2") (pinfunction "2_2") (pintype "passive"))
      (node (ref "IC1") (pin "4") (pinfunction "-Vout_4") (pintype "power_in"))
      (node (ref "IC6") (pin "11") (pinfunction "-VOUT_11") (pintype "power_in"))
      (node (ref "L9") (pin "1") (pinfunction "1_1") (pintype "passive"))
      (node (ref "R27") (pin "1") (pinfunction "1_1") (pintype "passive"))
      (node (ref "R4") (pin "1") (pinfunction "1_1") (pintype "passive"))
    )
    (net (code "2") (name "/N_LDO_EN") (class "Default")
      (node (ref "C32") (pin "2") (pinfunction "2_2") (pintype "passive"))
      (node (ref "IC11") (pin "4") (pinfunction "~{SHDN}_4") (pintype "input"))
      (node (ref "IC12") (pin "6") (pinfunction "~{RESET}_6") (pintype "passive"))
      (node (ref "R35") (pin "2") (pinfunction "2_2") (pintype "passive"))
    )
    (net (code "3") (name "/P3V3_PSEQ") (class "Default")
      (node (ref "C30") (pin "2") (pinfunction "2_2") (pintype "passive"))
      (node (ref "C35") (pin "2") (pinfunction "2_2") (pintype "passive"))
      (node (ref "IC12") (pin "4") (pinfunction "VDD_4") (pintype "passive"))
      (node (ref "IC13") (pin "4") (pinfunction "VDD_4") (pintype "passive"))
      (node (ref "IC14") (pin "1") (pinfunction "C_1") (pintype "passive"))
      (node (ref "R35") (pin "1") (pinfunction "1_1") (pintype "passive"))
      (node (ref "R36") (pin "1") (pinfunction "1_1") (pintype "passive"))
      (node (ref "R37") (pin "2") (pinfunction "2_2") (pintype "passive"))
      (node (ref "R39") (pin "1") (pinfunction "1_1") (pintype "passive"))
      (node (ref "R41") (pin "2") (pinfunction "2_2") (pintype "passive"))
      (node (ref "R42") (pin "2") (pinfunction "2_2") (pintype "passive"))
    )
    (net (code "4") (name "/P13V0") (class "Default")
      (node (ref "C130") (pin "2") (pinfunction "2_2") (pintype "passive"))
      (node (ref "IC1") (pin "7") (pinfunction "+Vout_7") (pintype "power_in"))
      (node (ref "IC6") (pin "14") (pinfunction "+VOUT_14") (pintype "power_in"))
      (node (ref "L6") (pin "1") (pinfunction "1_1") (pintype "passive"))
      (node (ref "R1") (pin "2") (pinfunction "2_2") (pintype "passive"))
      (node (ref "R26") (pin "2") (pinfunction "2_2") (pintype "passive"))
    )
    (net (code "5") (name "/P_LDO_EN") (class "Default")
      (node (ref "C36") (pin "2") (pinfunction "2_2") (pintype "passive"))
      (node (ref "IC13") (pin "6") (pinfunction "~{RESET}_6") (pintype "passive"))
      (node (ref "IC27") (pin "5") (pinfunction "~{SHDN}_5") (pintype "input"))
      (node (ref "R39") (pin "2") (pinfunction "2_2") (pintype "passive"))
    )
    (net (code "6") (name "GND") (class "Default")
      (node (ref "C10") (pin "2") (pinfunction "2_2") (pintype "passive"))
      (node (ref "C124") (pin "2") (pinfunction "2_2") (pintype "passive"))
      (node (ref "C129") (pin "1") (pinfunction "1_1") (pintype "passive"))
      (node (ref "C130") (pin "1") (pinfunction "1_1") (pintype "passive"))
      (node (ref "C131") (pin "1") (pinfunction "1_1") (pintype "passive"))
      (node (ref "C132") (pin "2") (pinfunction "2_2") (pintype "passive"))
      (node (ref "C133") (pin "1") (pinfunction "1_1") (pintype "passive"))
      (node (ref "C134") (pin "2") (pinfunction "2_2") (pintype "passive"))
      (node (ref "C136") (pin "2") (pinfunction "2_2") (pintype "passive"))
      (node (ref "C137") (pin "1") (pinfunction "1_1") (pintype "passive"))
      (node (ref "C138") (pin "1") (pinfunction "1_1") (pintype "passive"))
      (node (ref "C139") (pin "1") (pinfunction "1_1") (pintype "passive"))
      (node (ref "C140") (pin "1") (pinfunction "1_1") (pintype "passive"))
      (node (ref "C141") (pin "1") (pinfunction "1_1") (pintype "passive"))
      (node (ref "C142") (pin "1") (pinfunction "1_1") (pintype "passive"))
      (node (ref "C144") (pin "1") (pinfunction "1_1") (pintype "passive"))
      (node (ref "C147") (pin "1") (pinfunction "1_1") (pintype "passive"))
      (node (ref "C148") (pin "1") (pinfunction "1_1") (pintype "passive"))
      (node (ref "C149") (pin "1") (pinfunction "1_1") (pintype "passive"))
      (node (ref "C150") (pin "1") (pinfunction "1_1") (pintype "passive"))
      (node (ref "C151") (pin "1") (pinfunction "1_1") (pintype "passive"))
      (node (ref "C17") (pin "1") (pinfunction "1_1") (pintype "passive"))
      (node (ref "C18") (pin "1") (pinfunction "1_1") (pintype "passive"))
      (node (ref "C2") (pin "1") (pinfunction "1_1") (pintype "passive"))
      (node (ref "C25") (pin "1") (pinfunction "1_1") (pintype "passive"))
      (node (ref "C26") (pin "1") (pinfunction "1_1") (pintype "passive"))
      (node (ref "C28") (pin "1") (pinfunction "1_1") (pintype "passive"))
      (node (ref "C29") (pin "1") (pinfunction "1_1") (pintype "passive"))
      (node (ref "C3") (pin "1") (pinfunction "1_1") (pintype "passive"))
      (node (ref "C30") (pin "1") (pinfunction "1_1") (pintype "passive"))
      (node (ref "C32") (pin "1") (pinfunction "1_1") (pintype "passive"))
      (node (ref "C34") (pin "1") (pinfunction "1_1") (pintype "passive"))
      (node (ref "C35") (pin "1") (pinfunction "1_1") (pintype "passive"))
      (node (ref "C36") (pin "1") (pinfunction "1_1") (pintype "passive"))
      (node (ref "C37") (pin "1") (pinfunction "1_1") (pintype "passive"))
      (node (ref "C4") (pin "1") (pinfunction "1_1") (pintype "passive"))
      (node (ref "C5") (pin "1") (pinfunction "1_1") (pintype "passive"))
      (node (ref "C63") (pin "1") (pinfunction "1_1") (pintype "passive"))
      (node (ref "D1") (pin "2") (pinfunction "A_2") (pintype "passive"))
      (node (ref "D2") (pin "1") (pinfunction "C_1") (pintype "passive"))
      (node (ref "IC1") (pin "3") (pinfunction "-Vin_3") (pintype "power_in"))
      (node (ref "IC1") (pin "5") (pinfunction "COM_5") (pintype "power_in"))
      (node (ref "IC1") (pin "8") (pinfunction "Shield_8") (pintype "power_in"))
      (node (ref "IC11") (pin "6") (pinfunction "GND_6") (pintype "power_in"))
      (node (ref "IC12") (pin "2") (pinfunction "GND_2") (pintype "passive"))
      (node (ref "IC13") (pin "2") (pinfunction "GND_2") (pintype "passive"))
      (node (ref "IC14") (pin "2") (pinfunction "A_2") (pintype "passive"))
      (node (ref "IC27") (pin "3") (pinfunction "GND_3") (pintype "power_in"))
      (node (ref "IC27") (pin "6") (pinfunction "GND_6") (pintype "power_in"))
      (node (ref "IC27") (pin "7") (pinfunction "GND_7") (pintype "power_in"))
      (node (ref "IC35") (pin "1") (pinfunction "PGND_1") (pintype "power_in"))
      (node (ref "IC35") (pin "11") (pinfunction "EP_11") (pintype "power_in"))
      (node (ref "IC35") (pin "6") (pinfunction "AGND_6") (pintype "power_in"))
      (node (ref "IC4") (pin "1") (pinfunction "GND_1") (pintype "power_in"))
      (node (ref "IC6") (pin "16") (pinfunction "COMMON_16") (pintype "power_in"))
      (node (ref "IC6") (pin "2") (pinfunction "-VIN_2") (pintype "power_in"))
      (node (ref "IC6") (pin "3") (pinfunction "-VIN_3") (pintype "power_in"))
      (node (ref "IC6") (pin "9") (pinfunction "COMMON_9") (pintype "power_in"))
      (node (ref "IC7") (pin "1") (pinfunction "GND_1") (pintype "power_in"))
      (node (ref "R153") (pin "1") (pinfunction "1_1") (pintype "passive"))
      (node (ref "R164") (pin "1") (pinfunction "1_1") (pintype "passive"))
      (node (ref "R2") (pin "1") (pinfunction "1_1") (pintype "passive"))
      (node (ref "R34") (pin "1") (pinfunction "1_1") (pintype "passive"))
      (node (ref "R40") (pin "1") (pinfunction "1_1") (pintype "passive"))
      (node (ref "R44") (pin "1") (pinfunction "1_1") (pintype "passive"))
      (node (ref "R70") (pin "1") (pinfunction "1_1") (pintype "passive"))
      (node (ref "TP6") (pin "1") (pinfunction "1_1") (pintype "bidirectional"))
      (node (ref "TP7") (pin "1") (pinfunction "1_1") (pintype "bidirectional"))
    )
    (net (code "7") (name "N12V0A") (class "Default")
      (node (ref "C147") (pin "2") (pinfunction "2_2") (pintype "passive"))
      (node (ref "C27") (pin "1") (pinfunction "1_1") (pintype "passive"))
      (node (ref "C29") (pin "2") (pinfunction "2_2") (pintype "passive"))
      (node (ref "C5") (pin "2") (pinfunction "2_2") (pintype "passive"))
      (node (ref "C6") (pin "1") (pinfunction "1_1") (pintype "passive"))
      (node (ref "D2") (pin "2") (pinfunction "A_2") (pintype "passive"))
      (node (ref "IC11") (pin "1") (pinfunction "OUT_1") (pintype "power_in"))
      (node (ref "IC11") (pin "2") (pinfunction "OUT_2") (pintype "power_in"))
      (node (ref "IC4") (pin "5") (pinfunction "OUT_5") (pintype "power_in"))
      (node (ref "R69") (pin "2") (pinfunction "2_2") (pintype "passive"))
      (node (ref "TP9") (pin "1") (pinfunction "1_1") (pintype "bidirectional"))
    )
    (net (code "8") (name "N13V0_SCSI") (class "Default")
      (node (ref "R32") (pin "2") (pinfunction "2_2") (pintype "passive"))
    )
    (net (code "9") (name "Net-(C131-Pad2)") (class "Default")
      (node (ref "C131") (pin "2") (pinfunction "2_2") (pintype "passive"))
      (node (ref "C132") (pin "1") (pinfunction "1_1") (pintype "passive"))
      (node (ref "L6") (pin "2") (pinfunction "2_2") (pintype "passive"))
      (node (ref "L7") (pin "1") (pinfunction "1_1") (pintype "passive"))
      (node (ref "R31") (pin "1") (pinfunction "1_1") (pintype "passive"))
    )
    (net (code "10") (name "Net-(C142-Pad2)") (class "Default")
      (node (ref "C142") (pin "2") (pinfunction "2_2") (pintype "passive"))
      (node (ref "C2") (pin "2") (pinfunction "2_2") (pintype "passive"))
      (node (ref "L15") (pin "1") (pinfunction "1_1") (pintype "passive"))
      (node (ref "L9") (pin "2") (pinfunction "2_2") (pintype "passive"))
      (node (ref "R32") (pin "1") (pinfunction "1_1") (pintype "passive"))
    )
    (net (code "11") (name "Net-(IC1-+Vin)") (class "Default")
      (node (ref "C136") (pin "1") (pinfunction "1_1") (pintype "passive"))
      (node (ref "C137") (pin "2") (pinfunction "2_2") (pintype "passive"))
      (node (ref "C138") (pin "2") (pinfunction "2_2") (pintype "passive"))
      (node (ref "C139") (pin "2") (pinfunction "2_2") (pintype "passive"))
      (node (ref "C140") (pin "2") (pinfunction "2_2") (pintype "passive"))
      (node (ref "C150") (pin "2") (pinfunction "2_2") (pintype "passive"))
      (node (ref "C151") (pin "2") (pinfunction "2_2") (pintype "passive"))
      (node (ref "C17") (pin "2") (pinfunction "2_2") (pintype "passive"))
      (node (ref "C18") (pin "2") (pinfunction "2_2") (pintype "passive"))
      (node (ref "IC1") (pin "1") (pinfunction "+Vin_1") (pintype "power_in"))
      (node (ref "IC35") (pin "2") (pinfunction "VIN_2") (pintype "input"))
      (node (ref "IC35") (pin "3") (pinfunction "EN_3") (pintype "input"))
      (node (ref "IC6") (pin "22") (pinfunction "+VIN_22") (pintype "power_in"))
      (node (ref "IC6") (pin "23") (pinfunction "+VIN_23") (pintype "power_in"))
      (node (ref "IC7") (pin "3") (pinfunction "VIN_3") (pintype "input"))
      (node (ref "L8") (pin "1") (pinfunction "1_1") (pintype "passive"))
    )
    (net (code "12") (name "Net-(IC1-RC)") (class "Default")
      (node (ref "IC1") (pin "2") (pinfunction "RC_2") (pintype "input"))
      (node (ref "R2") (pin "2") (pinfunction "2_2") (pintype "passive"))
    )
    (net (code "13") (name "Net-(IC1-TRM)") (class "Default")
      (node (ref "IC1") (pin "6") (pinfunction "TRM_6") (pintype "power_in"))
      (node (ref "R1") (pin "1") (pinfunction "1_1") (pintype "passive"))
      (node (ref "R4") (pin "2") (pinfunction "2_2") (pintype "passive"))
    )
    (net (code "14") (name "Net-(IC4-BYP)") (class "Default")
      (node (ref "C6") (pin "2") (pinfunction "2_2") (pintype "passive"))
      (node (ref "IC4") (pin "3") (pinfunction "BYP_3") (pintype "input"))
    )
    (net (code "15") (name "Net-(IC4-IN)") (class "Default")
      (node (ref "C144") (pin "2") (pinfunction "2_2") (pintype "passive"))
      (node (ref "C28") (pin "2") (pinfunction "2_2") (pintype "passive"))
      (node (ref "C3") (pin "2") (pinfunction "2_2") (pintype "passive"))
      (node (ref "IC11") (pin "7") (pinfunction "IN_7") (pintype "power_in"))
      (node (ref "IC11") (pin "8") (pinfunction "IN_8") (pintype "power_in"))
      (node (ref "IC11") (pin "9") (pinfunction "IN_9") (pintype "power_in"))
      (node (ref "IC4") (pin "2") (pinfunction "IN_2") (pintype "input"))
      (node (ref "L15") (pin "2") (pinfunction "2_2") (pintype "passive"))
    )
    (net (code "16") (name "Net-(IC6-TRIM)") (class "Default")
      (node (ref "IC6") (pin "10") (pinfunction "TRIM_10") (pintype "power_in"))
      (node (ref "R26") (pin "1") (pinfunction "1_1") (pintype "passive"))
      (node (ref "R27") (pin "2") (pinfunction "2_2") (pintype "passive"))
    )
    (net (code "17") (name "Net-(IC7-BST)") (class "Default")
      (node (ref "C16") (pin "1") (pinfunction "1_1") (pintype "passive"))
      (node (ref "IC7") (pin "6") (pinfunction "BST_6") (pintype "input"))
    )
    (net (code "18") (name "Net-(IC7-FB)") (class "Default")
      (node (ref "IC7") (pin "4") (pinfunction "FB_4") (pintype "input"))
      (node (ref "R33") (pin "1") (pinfunction "1_1") (pintype "passive"))
      (node (ref "R34") (pin "2") (pinfunction "2_2") (pintype "passive"))
    )
    (net (code "19") (name "Net-(IC7-SW)") (class "Default")
      (node (ref "C16") (pin "2") (pinfunction "2_2") (pintype "passive"))
      (node (ref "IC7") (pin "2") (pinfunction "SW_2") (pintype "output"))
      (node (ref "L2") (pin "1") (pinfunction "1_1") (pintype "passive"))
    )
    (net (code "20") (name "Net-(IC11-ADJ)") (class "Default")
      (node (ref "IC11") (pin "3") (pinfunction "ADJ_3") (pintype "input"))
      (node (ref "IC4") (pin "4") (pinfunction "ADJ_4") (pintype "input"))
      (node (ref "R69") (pin "1") (pinfunction "1_1") (pintype "passive"))
      (node (ref "R70") (pin "2") (pinfunction "2_2") (pintype "passive"))
    )
    (net (code "21") (name "Net-(IC11-BYP)") (class "Default")
      (node (ref "C27") (pin "2") (pinfunction "2_2") (pintype "passive"))
      (node (ref "IC11") (pin "5") (pinfunction "BYP_5") (pintype "passive"))
    )
    (net (code "22") (name "Net-(IC12-CT)") (class "Default")
      (node (ref "C34") (pin "2") (pinfunction "2_2") (pintype "passive"))
      (node (ref "IC12") (pin "5") (pinfunction "CT_5") (pintype "passive"))
    )
    (net (code "23") (name "Net-(IC12-SENSE)") (class "Default")
      (node (ref "IC12") (pin "1") (pinfunction "SENSE_1") (pintype "passive"))
      (node (ref "R43") (pin "1") (pinfunction "1_1") (pintype "passive"))
      (node (ref "R44") (pin "2") (pinfunction "2_2") (pintype "passive"))
    )
    (net (code "24") (name "Net-(IC12-~{MR})") (class "Default")
      (node (ref "IC12") (pin "3") (pinfunction "~{MR}_3") (pintype "passive"))
      (node (ref "R37") (pin "1") (pinfunction "1_1") (pintype "passive"))
    )
    (net (code "25") (name "Net-(IC13-CT)") (class "Default")
      (node (ref "C37") (pin "2") (pinfunction "2_2") (pintype "passive"))
      (node (ref "IC13") (pin "5") (pinfunction "CT_5") (pintype "passive"))
    )
    (net (code "26") (name "Net-(IC13-SENSE)") (class "Default")
      (node (ref "IC13") (pin "1") (pinfunction "SENSE_1") (pintype "passive"))
      (node (ref "R38") (pin "1") (pinfunction "1_1") (pintype "passive"))
      (node (ref "R40") (pin "2") (pinfunction "2_2") (pintype "passive"))
    )
    (net (code "27") (name "Net-(IC13-~{MR})") (class "Default")
      (node (ref "IC13") (pin "3") (pinfunction "~{MR}_3") (pintype "passive"))
      (node (ref "R41") (pin "1") (pinfunction "1_1") (pintype "passive"))
    )
    (net (code "28") (name "Net-(IC27-ADJ)") (class "Default")
      (node (ref "IC27") (pin "2") (pinfunction "ADJ_2") (pintype "input"))
      (node (ref "R150") (pin "1") (pinfunction "1_1") (pintype "passive"))
      (node (ref "R153") (pin "2") (pinfunction "2_2") (pintype "passive"))
    )
    (net (code "29") (name "Net-(IC27-BYP)") (class "Default")
      (node (ref "C64") (pin "1") (pinfunction "1_1") (pintype "passive"))
      (node (ref "IC27") (pin "4") (pinfunction "BYP_4") (pintype "passive"))
    )
    (net (code "30") (name "Net-(IC27-IN)") (class "Default")
      (node (ref "C133") (pin "2") (pinfunction "2_2") (pintype "passive"))
      (node (ref "C134") (pin "1") (pinfunction "1_1") (pintype "passive"))
      (node (ref "C63") (pin "2") (pinfunction "2_2") (pintype "passive"))
      (node (ref "IC27") (pin "8") (pinfunction "IN_8") (pintype "input"))
      (node (ref "L7") (pin "2") (pinfunction "2_2") (pintype "passive"))
      (node (ref "R36") (pin "2") (pinfunction "2_2") (pintype "passive"))
      (node (ref "R38") (pin "2") (pinfunction "2_2") (pintype "passive"))
    )
    (net (code "31") (name "Net-(IC35-FB)") (class "Default")
      (node (ref "IC35") (pin "5") (pinfunction "FB_5") (pintype "input"))
      (node (ref "R162") (pin "1") (pinfunction "1_1") (pintype "passive"))
      (node (ref "R164") (pin "2") (pinfunction "2_2") (pintype "passive"))
    )
    (net (code "32") (name "Net-(IC35-SW)") (class "Default")
      (node (ref "IC35") (pin "9") (pinfunction "SW_9") (pintype "output"))
      (node (ref "L16") (pin "1") (pinfunction "1_1") (pintype "passive"))
    )
    (net (code "33") (name "P3V3") (class "Default")
      (node (ref "C148") (pin "2") (pinfunction "2_2") (pintype "passive"))
      (node (ref "C149") (pin "2") (pinfunction "2_2") (pintype "passive"))
      (node (ref "C25") (pin "2") (pinfunction "2_2") (pintype "passive"))
      (node (ref "C26") (pin "2") (pinfunction "2_2") (pintype "passive"))
      (node (ref "IC35") (pin "10") (pinfunction "VOS_10") (pintype "input"))
      (node (ref "IC35") (pin "8") (pinfunction "SLEEP_8") (pintype "input"))
      (node (ref "L16") (pin "2") (pinfunction "2_2") (pintype "passive"))
      (node (ref "L2") (pin "2") (pinfunction "2_2") (pintype "passive"))
      (node (ref "R162") (pin "2") (pinfunction "2_2") (pintype "passive"))
      (node (ref "R33") (pin "2") (pinfunction "2_2") (pintype "passive"))
      (node (ref "R42") (pin "1") (pinfunction "1_1") (pintype "passive"))
      (node (ref "TP10") (pin "1") (pinfunction "1_1") (pintype "bidirectional"))
    )
    (net (code "34") (name "P12V0") (class "Default")
      (node (ref "C10") (pin "1") (pinfunction "1_1") (pintype "passive"))
      (node (ref "C129") (pin "2") (pinfunction "2_2") (pintype "passive"))
      (node (ref "L8") (pin "2") (pinfunction "2_2") (pintype "passive"))
      (node (ref "R30") (pin "1") (pinfunction "1_1") (pintype "passive"))
    )
    (net (code "35") (name "P12V0A") (class "Default")
      (node (ref "C124") (pin "1") (pinfunction "1_1") (pintype "passive"))
      (node (ref "C4") (pin "2") (pinfunction "2_2") (pintype "passive"))
      (node (ref "C64") (pin "2") (pinfunction "2_2") (pintype "passive"))
      (node (ref "D1") (pin "1") (pinfunction "C_1") (pintype "passive"))
      (node (ref "IC27") (pin "1") (pinfunction "OUT_1") (pintype "power_in"))
      (node (ref "R150") (pin "2") (pinfunction "2_2") (pintype "passive"))
      (node (ref "R43") (pin "2") (pinfunction "2_2") (pintype "passive"))
      (node (ref "TP8") (pin "1") (pinfunction "1_1") (pintype "bidirectional"))
    )
    (net (code "36") (name "P13V0_SCSI") (class "Default")
      (node (ref "R30") (pin "2") (pinfunction "2_2") (pintype "passive"))
      (node (ref "R31") (pin "2") (pinfunction "2_2") (pintype "passive"))
    )
    (net (code "37") (name "unconnected-(IC7-EN-Pad5)") (class "Default")
      (node (ref "IC7") (pin "5") (pinfunction "EN_5") (pintype "input+no_connect"))
    )
    (net (code "38") (name "unconnected-(IC35-NC-Pad4)") (class "Default")
      (node (ref "IC35") (pin "4") (pinfunction "NC_4") (pintype "passive"))
    )
    (net (code "39") (name "unconnected-(IC35-PG-Pad7)") (class "Default")
      (node (ref "IC35") (pin "7") (pinfunction "PG_7") (pintype "output"))
    )
  )
)
